# Nintendo_3DS_USB-C.net
KiCad netlist of a schematic drawn in EAGLE
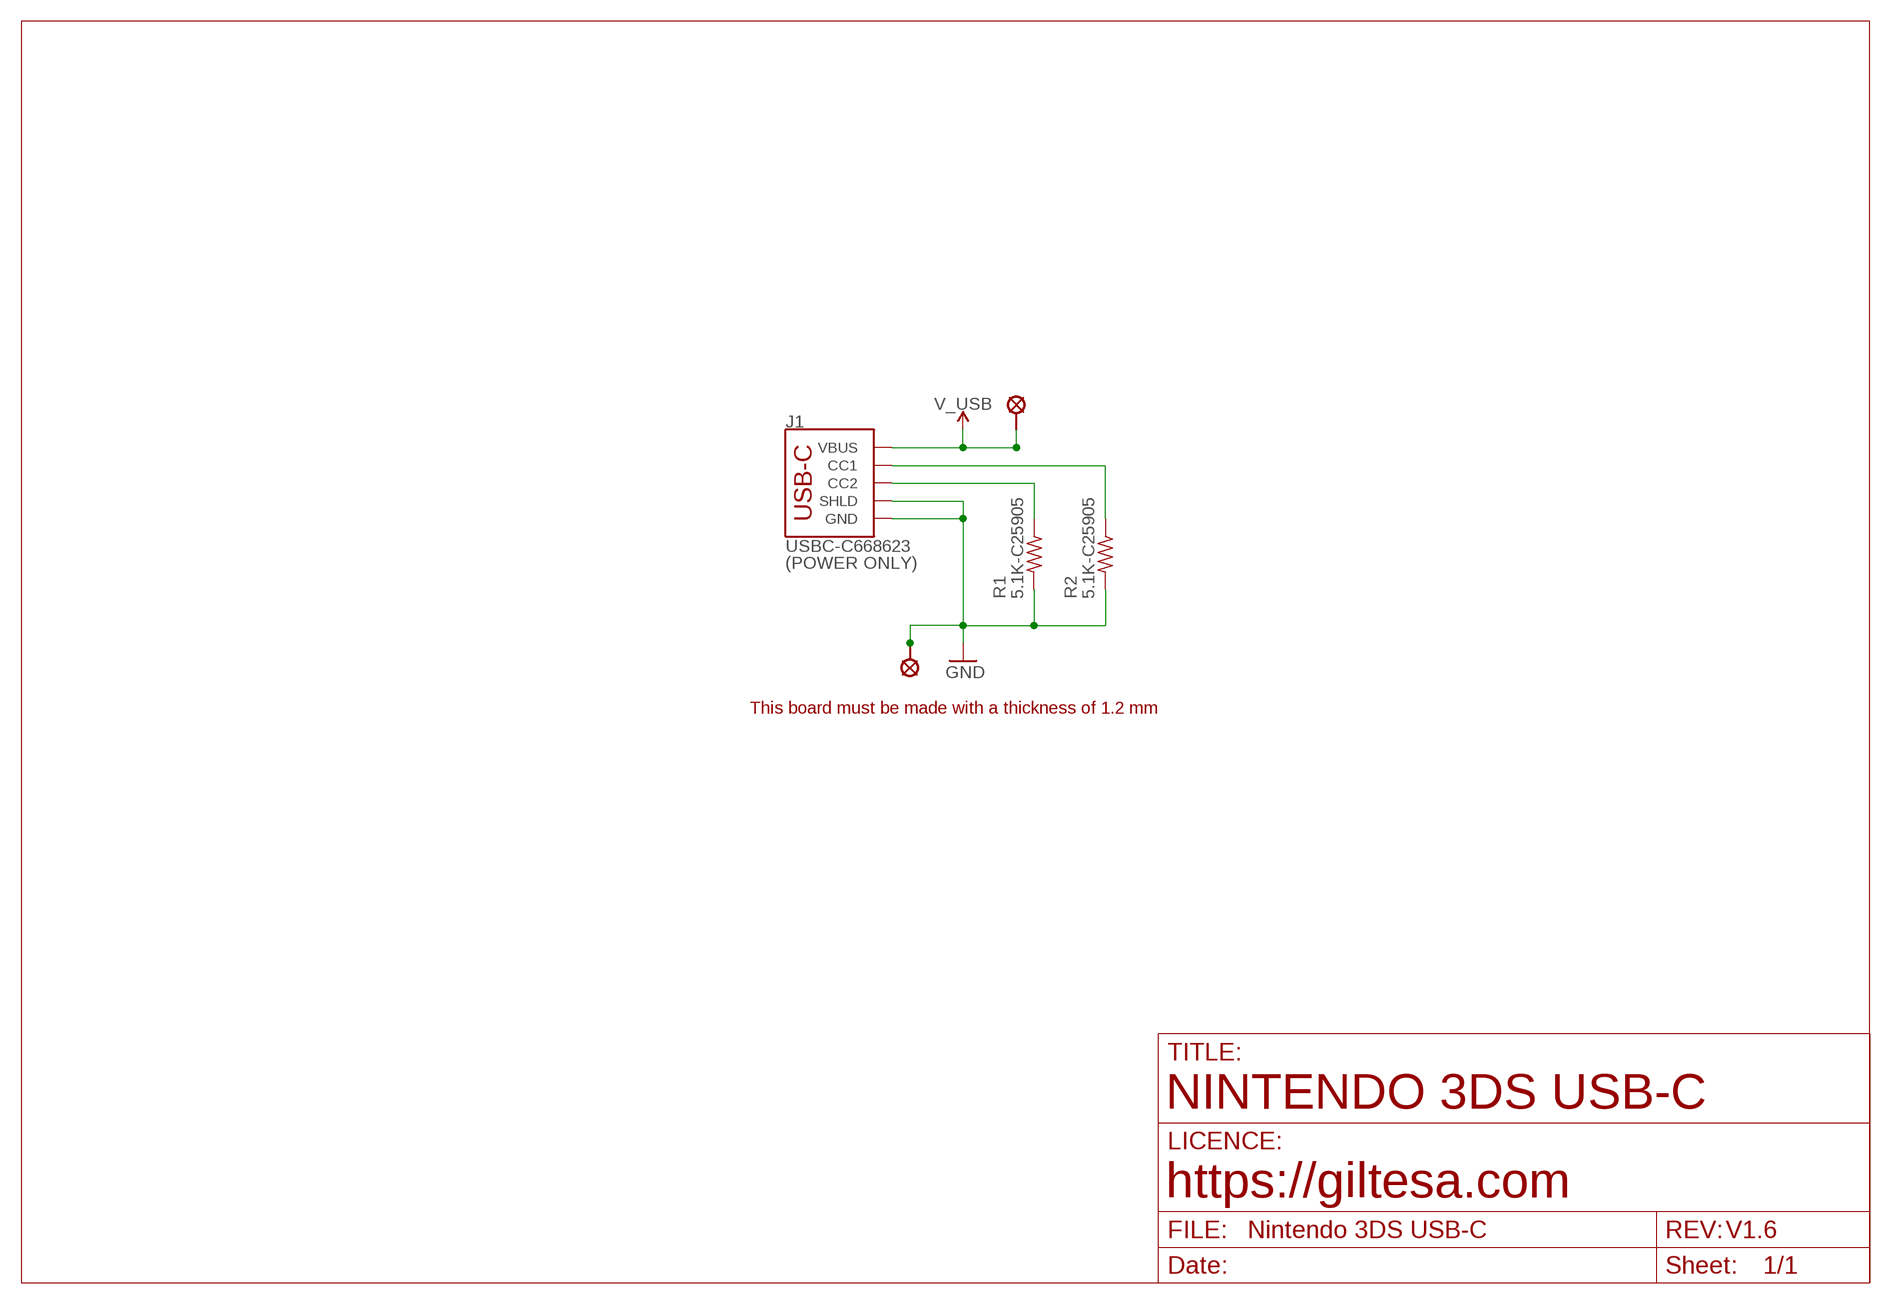
[diagram p0: schematic, sheet 1]

(export (version "E")
  (design (tool "Eeschema 10.0.6"))
  (components
    (comp (ref "J1")
      (value "USBC-C668623")
      (footprint "eagle-import:USB-C_6P")
      (libsource (lib "eagle-import") (part "USB-CPOWER"))
    )
    (comp (ref "R1")
      (value "5.1K-C25905")
      (footprint "eagle-import:R0402")
      (libsource (lib "eagle-import") (part "R0402"))
    )
    (comp (ref "R2")
      (value "5.1K-C25905")
      (footprint "eagle-import:R0402")
      (libsource (lib "eagle-import") (part "R0402"))
    )
    (comp (ref "U$2")
      (value "PAD_1.0")
      (footprint "eagle-import:PAD_1.0")
      (libsource (lib "eagle-import") (part "PAD_1.0"))
    )
    (comp (ref "U$3")
      (value "PAD_1.0")
      (footprint "eagle-import:PAD_1.0")
      (libsource (lib "eagle-import") (part "PAD_1.0"))
    )
    (comp (ref "U$4")
      (value "PAD_1.0")
      (footprint "eagle-import:PAD_1.0")
      (libsource (lib "eagle-import") (part "PAD_1.0"))
    )
    (comp (ref "U$6")
      (value "PAD_1.0")
      (footprint "eagle-import:PAD_1.0")
      (libsource (lib "eagle-import") (part "PAD_1.0"))
    )
    (comp (ref "U$7")
      (value "PAD_1.0")
      (footprint "eagle-import:PAD_1.0")
      (libsource (lib "eagle-import") (part "PAD_1.0"))
    )
    (comp (ref "U$8")
      (value "PAD_1.0")
      (footprint "eagle-import:PAD_1.0")
      (libsource (lib "eagle-import") (part "PAD_1.0"))
    )
  )
  (nets
    (net (code "1") (name "GND") (class "Default")
      (node (ref "J1") (pin "GND1") (pinfunction "GND_GND1") (pintype "bidirectional"))
      (node (ref "J1") (pin "GND2") (pinfunction "GND_GND2") (pintype "bidirectional"))
      (node (ref "J1") (pin "SHLD1") (pinfunction "SHLD_SHLD1") (pintype "bidirectional"))
      (node (ref "J1") (pin "SHLD2") (pinfunction "SHLD_SHLD2") (pintype "bidirectional"))
      (node (ref "J1") (pin "SHLD3") (pinfunction "SHLD_SHLD3") (pintype "bidirectional"))
      (node (ref "J1") (pin "SHLD4") (pinfunction "SHLD_SHLD4") (pintype "bidirectional"))
      (node (ref "J1") (pin "SHLD5") (pinfunction "SHLD_SHLD5") (pintype "bidirectional"))
      (node (ref "J1") (pin "SHLD6") (pinfunction "SHLD_SHLD6") (pintype "bidirectional"))
      (node (ref "J1") (pin "SHLD7") (pinfunction "SHLD_SHLD7") (pintype "bidirectional"))
      (node (ref "J1") (pin "SHLD8") (pinfunction "SHLD_SHLD8") (pintype "bidirectional"))
      (node (ref "R1") (pin "2") (pinfunction "2_2") (pintype "passive"))
      (node (ref "R2") (pin "2") (pinfunction "2_2") (pintype "passive"))
      (node (ref "U$4") (pin "P$1") (pinfunction "P$1_P$1") (pintype "bidirectional"))
      (node (ref "U$6") (pin "P$1") (pinfunction "P$1_P$1") (pintype "bidirectional"))
      (node (ref "U$7") (pin "P$1") (pinfunction "P$1_P$1") (pintype "bidirectional"))
      (node (ref "U$8") (pin "P$1") (pinfunction "P$1_P$1") (pintype "bidirectional"))
    )
    (net (code "2") (name "Net-(J1-CC1)") (class "Default")
      (node (ref "J1") (pin "A5") (pinfunction "CC1_A5") (pintype "bidirectional"))
      (node (ref "R2") (pin "1") (pinfunction "1_1") (pintype "passive"))
    )
    (net (code "3") (name "Net-(J1-CC2)") (class "Default")
      (node (ref "J1") (pin "B5") (pinfunction "CC2_B5") (pintype "bidirectional"))
      (node (ref "R1") (pin "1") (pinfunction "1_1") (pintype "passive"))
    )
    (net (code "4") (name "V_USB") (class "Default")
      (node (ref "J1") (pin "VBUS1") (pinfunction "VBUS_VBUS1") (pintype "bidirectional"))
      (node (ref "J1") (pin "VBUS2") (pinfunction "VBUS_VBUS2") (pintype "bidirectional"))
      (node (ref "U$2") (pin "P$1") (pinfunction "P$1_P$1") (pintype "bidirectional"))
      (node (ref "U$3") (pin "P$1") (pinfunction "P$1_P$1") (pintype "bidirectional"))
    )
  )
)
